# 32-S297connection.net
KiCad netlist of a schematic drawn in Altium Designer
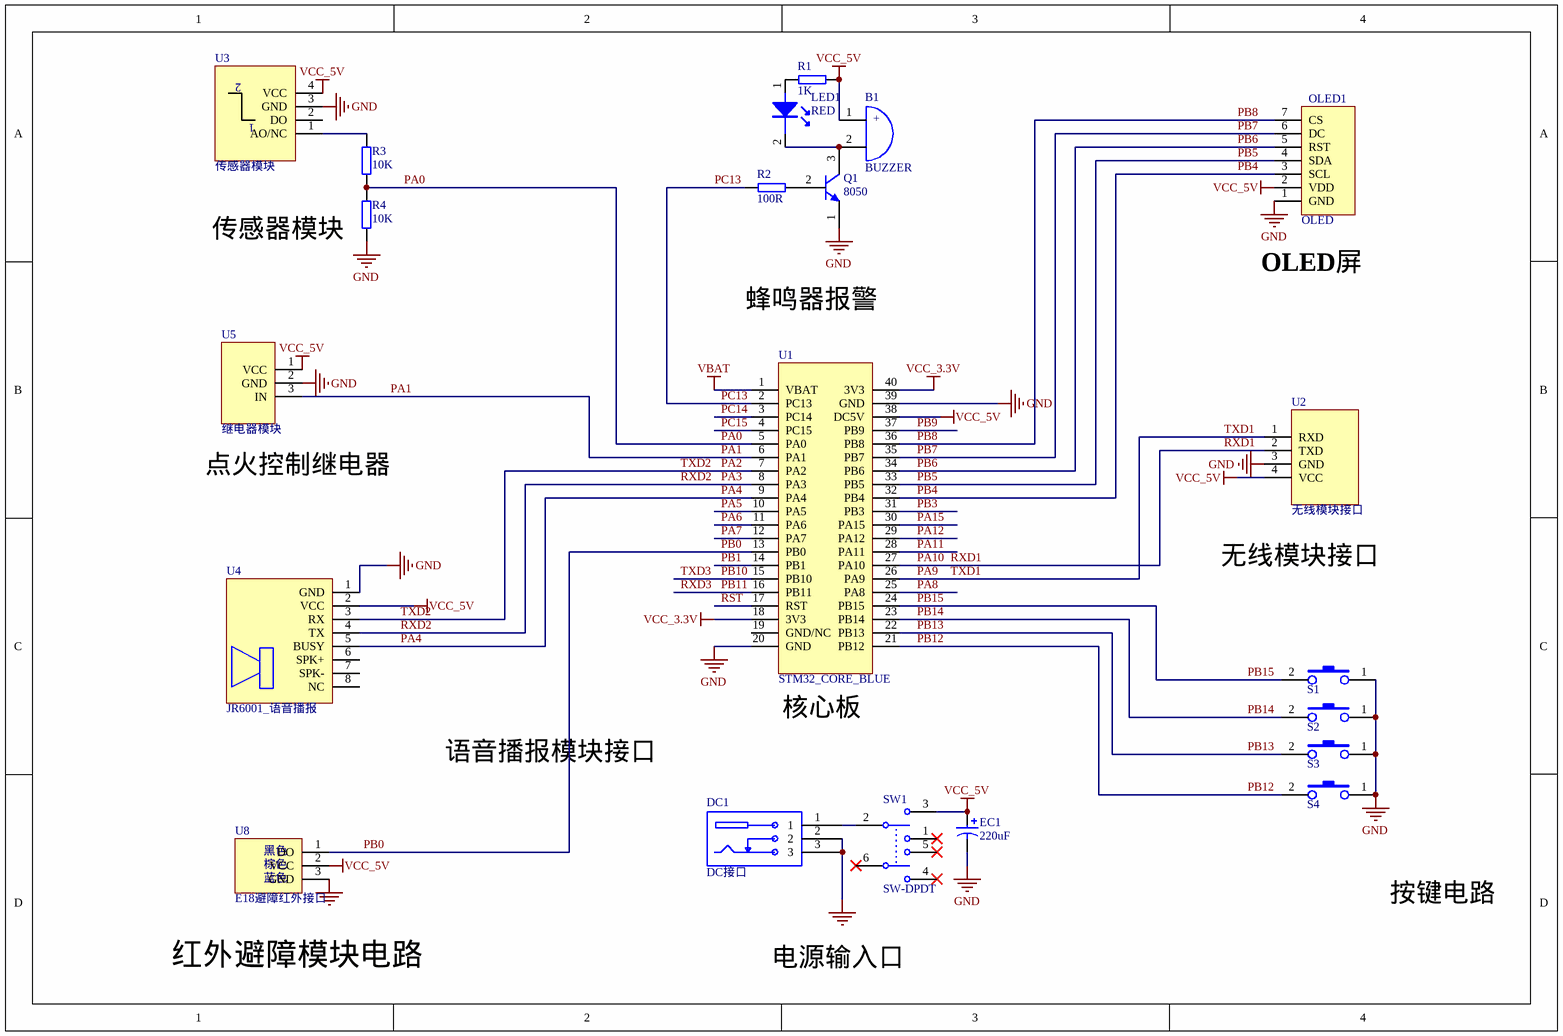
[diagram p0: 32-S297connection.SchDoc]

(export (version "E")
  (design (tool "Eeschema 10.0.6"))
  (components
    (comp (ref "B1")
      (value "BUZZER")
      (footprint "BUZZERSOT_PLASTIC")
      (description "蜂鸣器")
      (libsource (lib "参考") (part "BUZZER"))
    )
    (comp (ref "DC1")
      (value "DC接口")
      (footprint "DC-JACK-002")
      (description "DC接口（分大小）")
      (libsource (lib "参考") (part "DC接口"))
    )
    (comp (ref "EC1")
      (value "220uF")
      (footprint "RB.15/.3")
      (description "极性电容")
      (libsource (lib "参考") (part "CAP_EC"))
    )
    (comp (ref "LED1")
      (value "RED")
      (footprint "LED_D3MM12")
      (description "LED灯")
      (libsource (lib "TWKJ_S") (part "LED"))
    )
    (comp (ref "OLED1")
      (value "OLED")
      (footprint "TWKJ_S:OLED_0_96")
      (description "OLED-0.96")
      (libsource (lib "TWKJ_S") (part "OLED"))
    )
    (comp (ref "Q1")
      (value "8050")
      (footprint "TO-92")
      (description "三极管")
      (libsource (lib "参考") (part "9013"))
    )
    (comp (ref "R1")
      (value "1K")
      (footprint "AXIAL0.3")
      (description "电阻")
      (libsource (lib "TWKJ_S") (part "RES"))
    )
    (comp (ref "R2")
      (value "100R")
      (footprint "AXIAL0.3")
      (description "电阻")
      (libsource (lib "参考") (part "RES"))
    )
    (comp (ref "R3")
      (value "10K")
      (footprint "TWKJ_S:AXIAL0.3")
      (description "电阻")
      (libsource (lib "TWKJ_S") (part "RES"))
    )
    (comp (ref "R4")
      (value "10K")
      (footprint "TWKJ_S:AXIAL0.3")
      (description "电阻")
      (libsource (lib "TWKJ_S") (part "RES"))
    )
    (comp (ref "S1")
      (value "BUTTOM")
      (footprint "BUTTON_6x6DIP")
      (description "按键")
      (libsource (lib "参考") (part "BUTTOM"))
    )
    (comp (ref "S2")
      (value "BUTTOM")
      (footprint "BUTTON_6x6DIP")
      (description "按键")
      (libsource (lib "参考") (part "BUTTOM"))
    )
    (comp (ref "S3")
      (value "BUTTOM")
      (footprint "BUTTON_6x6DIP")
      (description "按键")
      (libsource (lib "参考") (part "BUTTOM"))
    )
    (comp (ref "S4")
      (value "BUTTOM")
      (footprint "BUTTON_6x6DIP")
      (description "按键")
      (libsource (lib "参考") (part "BUTTOM"))
    )
    (comp (ref "SW1")
      (value "SW-DPDT")
      (footprint "SW")
      (description "电源开关")
      (fields (field (name "PUBLISHER") "Altium Limited"))
      (libsource (lib "参考") (part "SW-DPDT"))
    )
    (comp (ref "U1")
      (value "STM32_CORE_BLUE")
      (footprint "STM32_CORE_BLUE")
      (libsource (lib "TWKJ_S") (part "STM32_CORE_BLUE"))
    )
    (comp (ref "U2")
      (value "无线模块接口")
      (footprint "蓝牙MODE竖放")
      (description "预留串口")
      (libsource (lib "参考") (part "蓝牙MODE"))
    )
    (comp (ref "U3")
      (value "传感器模块")
      (footprint "TWKJ_S:通用MODE竖放")
      (description "土壤湿度模块")
      (libsource (lib "TWKJ_S") (part "土壤检测MODE"))
    )
    (comp (ref "U4")
      (value "JR6001_语音播报")
      (footprint "JR6001_语音播报")
      (libsource (lib "TWKJ_S") (part "JR6001_语音播报"))
    )
    (comp (ref "U5") (value "继电器模块") (footprint "继电器接口") (libsource (lib "TWKJ_S") (part "继电器模块")))
    (comp (ref "U8")
      (value "E18避障红外接口")
      (footprint "TWKJ_S:红外接口")
      (description "避障红外探头模块")
      (libsource (lib "TWKJ_S") (part "避障红外接口"))
    )
  )
  (nets
    (net (code "1") (name "/PA0") (class "Default")
      (node (ref "R3") (pin "2") (pinfunction "2_2") (pintype "passive"))
      (node (ref "R4") (pin "1") (pinfunction "1_1") (pintype "passive"))
      (node (ref "U1") (pin "5") (pinfunction "PA0_5") (pintype "passive"))
    )
    (net (code "2") (name "/PA1") (class "Default")
      (node (ref "U1") (pin "6") (pinfunction "PA1_6") (pintype "passive"))
      (node (ref "U5") (pin "3") (pinfunction "IN_3") (pintype "passive"))
    )
    (net (code "3") (name "/PA2") (class "Default")
      (node (ref "U1") (pin "7") (pinfunction "PA2_7") (pintype "passive"))
      (node (ref "U4") (pin "3") (pinfunction "RX_3") (pintype "passive"))
    )
    (net (code "4") (name "/PA3") (class "Default")
      (node (ref "U1") (pin "8") (pinfunction "PA3_8") (pintype "passive"))
      (node (ref "U4") (pin "4") (pinfunction "TX_4") (pintype "passive"))
    )
    (net (code "5") (name "/PA4") (class "Default")
      (node (ref "U1") (pin "9") (pinfunction "PA4_9") (pintype "passive"))
      (node (ref "U4") (pin "5") (pinfunction "BUSY_5") (pintype "passive"))
    )
    (net (code "6") (name "/PA5") (class "Default")
      (node (ref "U1") (pin "10") (pinfunction "PA5_10") (pintype "passive"))
    )
    (net (code "7") (name "/PA6") (class "Default")
      (node (ref "U1") (pin "11") (pinfunction "PA6_11") (pintype "passive"))
    )
    (net (code "8") (name "/PA7") (class "Default")
      (node (ref "U1") (pin "12") (pinfunction "PA7_12") (pintype "passive"))
    )
    (net (code "9") (name "/PA8") (class "Default")
      (node (ref "U1") (pin "25") (pinfunction "PA8_25") (pintype "passive"))
    )
    (net (code "10") (name "/PA9") (class "Default")
      (node (ref "U1") (pin "26") (pinfunction "PA9_26") (pintype "passive"))
      (node (ref "U2") (pin "1") (pinfunction "RXD_1") (pintype "passive"))
    )
    (net (code "11") (name "/PA10") (class "Default")
      (node (ref "U1") (pin "27") (pinfunction "PA10_27") (pintype "passive"))
      (node (ref "U2") (pin "2") (pinfunction "TXD_2") (pintype "passive"))
    )
    (net (code "12") (name "/PA11") (class "Default")
      (node (ref "U1") (pin "28") (pinfunction "PA11_28") (pintype "passive"))
    )
    (net (code "13") (name "/PA12") (class "Default")
      (node (ref "U1") (pin "29") (pinfunction "PA12_29") (pintype "passive"))
    )
    (net (code "14") (name "/PA15") (class "Default")
      (node (ref "U1") (pin "30") (pinfunction "PA15_30") (pintype "passive"))
    )
    (net (code "15") (name "/PB0") (class "Default")
      (node (ref "U1") (pin "13") (pinfunction "PB0_13") (pintype "passive"))
      (node (ref "U8") (pin "1") (pinfunction "DO_1") (pintype "passive"))
    )
    (net (code "16") (name "/PB1") (class "Default")
      (node (ref "U1") (pin "14") (pinfunction "PB1_14") (pintype "passive"))
    )
    (net (code "17") (name "/PB3") (class "Default")
      (node (ref "U1") (pin "31") (pinfunction "PB3_31") (pintype "passive"))
    )
    (net (code "18") (name "/PB4") (class "Default")
      (node (ref "OLED1") (pin "3") (pinfunction "SCL_3") (pintype "passive"))
      (node (ref "U1") (pin "32") (pinfunction "PB4_32") (pintype "passive"))
    )
    (net (code "19") (name "/PB5") (class "Default")
      (node (ref "OLED1") (pin "4") (pinfunction "SDA_4") (pintype "passive"))
      (node (ref "U1") (pin "33") (pinfunction "PB5_33") (pintype "passive"))
    )
    (net (code "20") (name "/PB6") (class "Default")
      (node (ref "OLED1") (pin "5") (pinfunction "RST_5") (pintype "passive"))
      (node (ref "U1") (pin "34") (pinfunction "PB6_34") (pintype "passive"))
    )
    (net (code "21") (name "/PB7") (class "Default")
      (node (ref "OLED1") (pin "6") (pinfunction "DC_6") (pintype "passive"))
      (node (ref "U1") (pin "35") (pinfunction "PB7_35") (pintype "passive"))
    )
    (net (code "22") (name "/PB8") (class "Default")
      (node (ref "OLED1") (pin "7") (pinfunction "CS_7") (pintype "passive"))
      (node (ref "U1") (pin "36") (pinfunction "PB8_36") (pintype "passive"))
    )
    (net (code "23") (name "/PB9") (class "Default")
      (node (ref "U1") (pin "37") (pinfunction "PB9_37") (pintype "passive"))
    )
    (net (code "24") (name "/PB10") (class "Default")
      (node (ref "U1") (pin "15") (pinfunction "PB10_15") (pintype "passive"))
    )
    (net (code "25") (name "/PB11") (class "Default")
      (node (ref "U1") (pin "16") (pinfunction "PB11_16") (pintype "passive"))
    )
    (net (code "26") (name "/PB12") (class "Default")
      (node (ref "S4") (pin "2") (pinfunction "2_2") (pintype "passive"))
      (node (ref "U1") (pin "21") (pinfunction "PB12_21") (pintype "passive"))
    )
    (net (code "27") (name "/PB13") (class "Default")
      (node (ref "S3") (pin "2") (pinfunction "2_2") (pintype "passive"))
      (node (ref "U1") (pin "22") (pinfunction "PB13_22") (pintype "passive"))
    )
    (net (code "28") (name "/PB14") (class "Default")
      (node (ref "S2") (pin "2") (pinfunction "2_2") (pintype "passive"))
      (node (ref "U1") (pin "23") (pinfunction "PB14_23") (pintype "passive"))
    )
    (net (code "29") (name "/PB15") (class "Default")
      (node (ref "S1") (pin "2") (pinfunction "2_2") (pintype "passive"))
      (node (ref "U1") (pin "24") (pinfunction "PB15_24") (pintype "passive"))
    )
    (net (code "30") (name "/PC13") (class "Default")
      (node (ref "R2") (pin "2") (pinfunction "2_2") (pintype "passive"))
      (node (ref "U1") (pin "2") (pinfunction "PC13_2") (pintype "passive"))
    )
    (net (code "31") (name "/PC14") (class "Default")
      (node (ref "U1") (pin "3") (pinfunction "PC14_3") (pintype "passive"))
    )
    (net (code "32") (name "/PC15") (class "Default")
      (node (ref "U1") (pin "4") (pinfunction "PC15_4") (pintype "passive"))
    )
    (net (code "33") (name "/RST") (class "Default")
      (node (ref "U1") (pin "17") (pinfunction "RST_17") (pintype "passive"))
    )
    (net (code "34") (name "GND") (class "Default")
      (node (ref "DC1") (pin "2") (pinfunction "2_2") (pintype "passive"))
      (node (ref "DC1") (pin "3") (pinfunction "3_3") (pintype "passive"))
      (node (ref "EC1") (pin "2") (pinfunction "2_2") (pintype "passive"))
      (node (ref "OLED1") (pin "1") (pinfunction "GND_1") (pintype "passive"))
      (node (ref "Q1") (pin "1") (pinfunction "1_1") (pintype "passive"))
      (node (ref "R4") (pin "2") (pinfunction "2_2") (pintype "passive"))
      (node (ref "S1") (pin "1") (pinfunction "1_1") (pintype "passive"))
      (node (ref "S2") (pin "1") (pinfunction "1_1") (pintype "passive"))
      (node (ref "S3") (pin "1") (pinfunction "1_1") (pintype "passive"))
      (node (ref "S4") (pin "1") (pinfunction "1_1") (pintype "passive"))
      (node (ref "U1") (pin "20") (pinfunction "GND_20") (pintype "passive"))
      (node (ref "U1") (pin "39") (pinfunction "GND_39") (pintype "passive"))
      (node (ref "U2") (pin "3") (pinfunction "GND_3") (pintype "passive"))
      (node (ref "U3") (pin "3") (pinfunction "GND_3") (pintype "passive"))
      (node (ref "U4") (pin "1") (pinfunction "GND_1") (pintype "passive"))
      (node (ref "U5") (pin "2") (pinfunction "GND_2") (pintype "passive"))
      (node (ref "U8") (pin "3") (pinfunction "GND_3") (pintype "passive"))
    )
    (net (code "35") (name "Net-(B1-Pad2)") (class "Default")
      (node (ref "B1") (pin "2") (pinfunction "2_2") (pintype "passive"))
      (node (ref "LED1") (pin "2") (pinfunction "2_2") (pintype "passive"))
      (node (ref "Q1") (pin "3") (pinfunction "3_3") (pintype "passive"))
    )
    (net (code "36") (name "Net-(DC1-Pad1)") (class "Default")
      (node (ref "DC1") (pin "1") (pinfunction "1_1") (pintype "passive"))
      (node (ref "SW1") (pin "2") (pinfunction "2_2") (pintype "passive"))
    )
    (net (code "37") (name "Net-(LED1-Pad1)") (class "Default")
      (node (ref "LED1") (pin "1") (pinfunction "1_1") (pintype "passive"))
      (node (ref "R1") (pin "2") (pinfunction "2_2") (pintype "passive"))
    )
    (net (code "38") (name "Net-(Q1-Pad2)") (class "Default")
      (node (ref "Q1") (pin "2") (pinfunction "2_2") (pintype "passive"))
      (node (ref "R2") (pin "1") (pinfunction "1_1") (pintype "passive"))
    )
    (net (code "39") (name "Net-(U3-AO{slash}NC)") (class "Default")
      (node (ref "R3") (pin "1") (pinfunction "1_1") (pintype "passive"))
      (node (ref "U3") (pin "1") (pinfunction "AO/NC_1") (pintype "passive"))
    )
    (net (code "40") (name "VBAT") (class "Default")
      (node (ref "U1") (pin "1") (pinfunction "VBAT_1") (pintype "passive"))
    )
    (net (code "41") (name "VCC_3.3V") (class "Default")
      (node (ref "U1") (pin "18") (pinfunction "3V3_18") (pintype "passive"))
      (node (ref "U1") (pin "40") (pinfunction "3V3_40") (pintype "passive"))
    )
    (net (code "42") (name "VCC_5V") (class "Default")
      (node (ref "B1") (pin "1") (pinfunction "1_1") (pintype "passive"))
      (node (ref "EC1") (pin "1") (pinfunction "1_1") (pintype "passive"))
      (node (ref "OLED1") (pin "2") (pinfunction "VDD_2") (pintype "passive"))
      (node (ref "R1") (pin "1") (pinfunction "1_1") (pintype "passive"))
      (node (ref "SW1") (pin "3") (pinfunction "3_3") (pintype "passive"))
      (node (ref "U1") (pin "38") (pinfunction "DC5V_38") (pintype "passive"))
      (node (ref "U2") (pin "4") (pinfunction "VCC_4") (pintype "passive"))
      (node (ref "U3") (pin "4") (pinfunction "VCC_4") (pintype "passive"))
      (node (ref "U4") (pin "2") (pinfunction "VCC_2") (pintype "passive"))
      (node (ref "U5") (pin "1") (pinfunction "VCC_1") (pintype "passive"))
      (node (ref "U8") (pin "2") (pinfunction "VCC_2") (pintype "passive"))
    )
    (net (code "43") (name "unconnected-(SW1-Pad1)") (class "Default")
      (node (ref "SW1") (pin "1") (pinfunction "1_1") (pintype "passive+no_connect"))
    )
    (net (code "44") (name "unconnected-(SW1-Pad4)") (class "Default")
      (node (ref "SW1") (pin "4") (pinfunction "4_4") (pintype "passive+no_connect"))
    )
    (net (code "45") (name "unconnected-(SW1-Pad5)") (class "Default")
      (node (ref "SW1") (pin "5") (pinfunction "5_5") (pintype "passive+no_connect"))
    )
    (net (code "46") (name "unconnected-(SW1-Pad6)") (class "Default")
      (node (ref "SW1") (pin "6") (pinfunction "6_6") (pintype "passive+no_connect"))
    )
    (net (code "47") (name "unconnected-(U1-GND{slash}NC-Pad19)") (class "Default")
      (node (ref "U1") (pin "19") (pinfunction "GND/NC_19") (pintype "passive"))
    )
    (net (code "48") (name "unconnected-(U3-DO-Pad2)") (class "Default")
      (node (ref "U3") (pin "2") (pinfunction "DO_2") (pintype "passive"))
    )
    (net (code "49") (name "unconnected-(U4-NC-Pad8)") (class "Default")
      (node (ref "U4") (pin "8") (pinfunction "NC_8") (pintype "passive"))
    )
    (net (code "50") (name "unconnected-(U4-SPK+-Pad6)") (class "Default")
      (node (ref "U4") (pin "6") (pinfunction "SPK+_6") (pintype "passive"))
    )
    (net (code "51") (name "unconnected-(U4-SPK--Pad7)") (class "Default")
      (node (ref "U4") (pin "7") (pinfunction "SPK-_7") (pintype "passive"))
    )
  )
)
